# masterslavejk.net
KiCad netlist of a schematic drawn in EAGLE
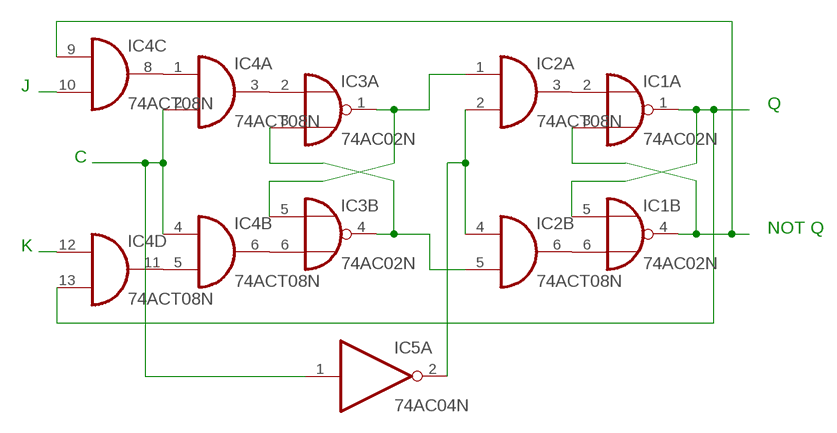
[diagram p0: schematic, sheet 1]

(export (version "E")
  (design (tool "Eeschema 10.0.6"))
  (components
    (comp (ref "IC1")
      (value "74AC02N")
      (footprint "eagle-import:DIL14")
      (libsource (lib "eagle-import") (part "7402NAC"))
    )
    (comp (ref "IC2")
      (value "74ACT08N")
      (footprint "eagle-import:DIL14")
      (libsource (lib "eagle-import") (part "7408NACT"))
    )
    (comp (ref "IC3")
      (value "74AC02N")
      (footprint "eagle-import:DIL14")
      (libsource (lib "eagle-import") (part "7402NAC"))
    )
    (comp (ref "IC4")
      (value "74ACT08N")
      (footprint "eagle-import:DIL14")
      (libsource (lib "eagle-import") (part "7408NACT"))
    )
    (comp (ref "IC5")
      (value "74AC04N")
      (footprint "eagle-import:DIL14")
      (libsource (lib "eagle-import") (part "7404NAC"))
    )
  )
  (nets
    (net (code "1") (name "Net-(IC1A-I0)") (class "Default")
      (node (ref "IC1") (pin "2") (pinfunction "I0_2") (pintype "input"))
      (node (ref "IC2") (pin "3") (pinfunction "O_3") (pintype "output"))
    )
    (net (code "2") (name "Net-(IC1A-I1)") (class "Default")
      (node (ref "IC1") (pin "3") (pinfunction "I1_3") (pintype "input"))
      (node (ref "IC1") (pin "4") (pinfunction "O_4") (pintype "output"))
      (node (ref "IC4") (pin "9") (pinfunction "I0_9") (pintype "input"))
    )
    (net (code "3") (name "Net-(IC1A-O)") (class "Default")
      (node (ref "IC1") (pin "1") (pinfunction "O_1") (pintype "output"))
      (node (ref "IC1") (pin "5") (pinfunction "I0_5") (pintype "input"))
      (node (ref "IC4") (pin "13") (pinfunction "I1_13") (pintype "input"))
    )
    (net (code "4") (name "Net-(IC1B-I1)") (class "Default")
      (node (ref "IC1") (pin "6") (pinfunction "I1_6") (pintype "input"))
      (node (ref "IC2") (pin "6") (pinfunction "O_6") (pintype "output"))
    )
    (net (code "5") (name "Net-(IC2A-I0)") (class "Default")
      (node (ref "IC2") (pin "1") (pinfunction "I0_1") (pintype "input"))
      (node (ref "IC3") (pin "1") (pinfunction "O_1") (pintype "output"))
      (node (ref "IC3") (pin "5") (pinfunction "I0_5") (pintype "input"))
    )
    (net (code "6") (name "Net-(IC2A-I1)") (class "Default")
      (node (ref "IC2") (pin "2") (pinfunction "I1_2") (pintype "input"))
      (node (ref "IC2") (pin "4") (pinfunction "I0_4") (pintype "input"))
      (node (ref "IC5") (pin "2") (pinfunction "O_2") (pintype "output"))
    )
    (net (code "7") (name "Net-(IC2B-I1)") (class "Default")
      (node (ref "IC2") (pin "5") (pinfunction "I1_5") (pintype "input"))
      (node (ref "IC3") (pin "3") (pinfunction "I1_3") (pintype "input"))
      (node (ref "IC3") (pin "4") (pinfunction "O_4") (pintype "output"))
    )
    (net (code "8") (name "Net-(IC3A-I0)") (class "Default")
      (node (ref "IC3") (pin "2") (pinfunction "I0_2") (pintype "input"))
      (node (ref "IC4") (pin "3") (pinfunction "O_3") (pintype "output"))
    )
    (net (code "9") (name "Net-(IC3B-I1)") (class "Default")
      (node (ref "IC3") (pin "6") (pinfunction "I1_6") (pintype "input"))
      (node (ref "IC4") (pin "6") (pinfunction "O_6") (pintype "output"))
    )
    (net (code "10") (name "Net-(IC4A-I0)") (class "Default")
      (node (ref "IC4") (pin "1") (pinfunction "I0_1") (pintype "input"))
      (node (ref "IC4") (pin "8") (pinfunction "O_8") (pintype "output"))
    )
    (net (code "11") (name "Net-(IC4A-I1)") (class "Default")
      (node (ref "IC4") (pin "2") (pinfunction "I1_2") (pintype "input"))
      (node (ref "IC4") (pin "4") (pinfunction "I0_4") (pintype "input"))
      (node (ref "IC5") (pin "1") (pinfunction "I_1") (pintype "input"))
    )
    (net (code "12") (name "Net-(IC4B-I1)") (class "Default")
      (node (ref "IC4") (pin "11") (pinfunction "O_11") (pintype "output"))
      (node (ref "IC4") (pin "5") (pinfunction "I1_5") (pintype "input"))
    )
    (net (code "13") (name "unconnected-(IC4C-I1-Pad10)") (class "Default")
      (node (ref "IC4") (pin "10") (pinfunction "I1_10") (pintype "input"))
    )
    (net (code "14") (name "unconnected-(IC4D-I0-Pad12)") (class "Default")
      (node (ref "IC4") (pin "12") (pinfunction "I0_12") (pintype "input"))
    )
  )
)
